# dac.net
KiCad netlist of a schematic drawn in EAGLE
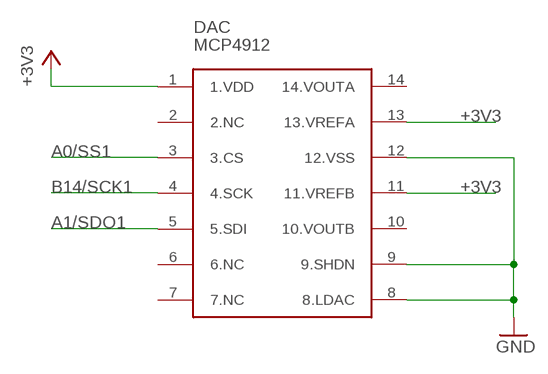
[diagram p0: schematic, sheet 1]
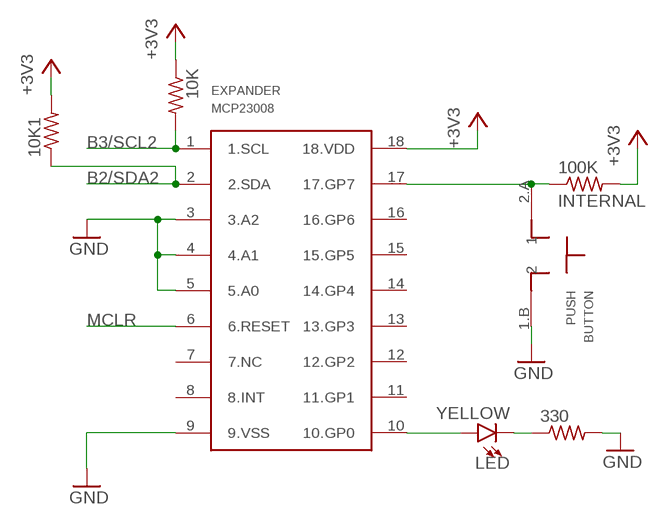
[diagram p1: schematic, sheet 2]

(export (version "E")
  (design (tool "Eeschema 10.0.6"))
  (components
    (comp (ref "DAC")
      (value "MCP4912")
      (footprint "eagle-import:MCP4912")
      (libsource (lib "eagle-import") (part "MCP4912"))
    )
    (comp (ref "10K")
      (value "R-US_R0603")
      (footprint "eagle-import:R0603")
      (libsource (lib "eagle-import") (part "R-US_R0603"))
    )
    (comp (ref "10K1")
      (value "R-US_R0603")
      (footprint "eagle-import:R0603")
      (libsource (lib "eagle-import") (part "R-US_R0603"))
    )
    (comp (ref "100K")
      (value "INTERNAL")
      (footprint "eagle-import:R0603")
      (libsource (lib "eagle-import") (part "R-US_R0603"))
    )
    (comp (ref "330")
      (value "R-US_R0603")
      (footprint "eagle-import:R0603")
      (libsource (lib "eagle-import") (part "R-US_R0603"))
    )
    (comp (ref "BUTTON")
      (value "PUSH")
      (footprint "eagle-import:NU32V7_MOM_SW")
      (libsource (lib "eagle-import") (part "PUSH"))
    )
    (comp (ref "EXPANDER")
      (value "MCP23008")
      (footprint "eagle-import:MCP23008")
      (libsource (lib "eagle-import") (part "MCP23008"))
    )
    (comp (ref "LED")
      (value "YELLOW")
      (footprint "eagle-import:LED-0603")
      (libsource (lib "eagle-import") (part "LED-RED0603"))
    )
  )
  (nets
    (net (code "1") (name "+3V3") (class "Default")
      (node (ref "100K") (pin "2") (pinfunction "2_2") (pintype "passive"))
      (node (ref "10K") (pin "1") (pinfunction "1_1") (pintype "passive"))
      (node (ref "10K1") (pin "2") (pinfunction "2_2") (pintype "passive"))
      (node (ref "DAC") (pin "1") (pinfunction "1.VDD_1") (pintype "bidirectional"))
      (node (ref "DAC") (pin "11") (pinfunction "11.VREFB_11") (pintype "bidirectional"))
      (node (ref "DAC") (pin "13") (pinfunction "13.VREFA_13") (pintype "bidirectional"))
      (node (ref "EXPANDER") (pin "18") (pinfunction "18.VDD_18") (pintype "bidirectional"))
    )
    (net (code "2") (name "A0{slash}SS1") (class "Default")
      (node (ref "DAC") (pin "3") (pinfunction "3.CS_3") (pintype "bidirectional"))
    )
    (net (code "3") (name "A1{slash}SDO1") (class "Default")
      (node (ref "DAC") (pin "5") (pinfunction "5.SDI_5") (pintype "bidirectional"))
    )
    (net (code "4") (name "B2{slash}SDA2") (class "Default")
      (node (ref "10K1") (pin "1") (pinfunction "1_1") (pintype "passive"))
      (node (ref "EXPANDER") (pin "2") (pinfunction "2.SDA_2") (pintype "bidirectional"))
    )
    (net (code "5") (name "B3{slash}SCL2") (class "Default")
      (node (ref "10K") (pin "2") (pinfunction "2_2") (pintype "passive"))
      (node (ref "EXPANDER") (pin "1") (pinfunction "1.SCL_1") (pintype "bidirectional"))
    )
    (net (code "6") (name "B14{slash}SCK1") (class "Default")
      (node (ref "DAC") (pin "4") (pinfunction "4.SCK_4") (pintype "bidirectional"))
    )
    (net (code "7") (name "GND") (class "Default")
      (node (ref "330") (pin "2") (pinfunction "2_2") (pintype "passive"))
      (node (ref "BUTTON") (pin "1.B") (pinfunction "2_1.B") (pintype "bidirectional"))
      (node (ref "DAC") (pin "12") (pinfunction "12.VSS_12") (pintype "bidirectional"))
      (node (ref "DAC") (pin "8") (pinfunction "8.LDAC_8") (pintype "bidirectional"))
      (node (ref "DAC") (pin "9") (pinfunction "9.SHDN_9") (pintype "bidirectional"))
      (node (ref "EXPANDER") (pin "3") (pinfunction "3.A2_3") (pintype "bidirectional"))
      (node (ref "EXPANDER") (pin "4") (pinfunction "4.A1_4") (pintype "bidirectional"))
      (node (ref "EXPANDER") (pin "5") (pinfunction "5.A0_5") (pintype "bidirectional"))
      (node (ref "EXPANDER") (pin "9") (pinfunction "9.VSS_9") (pintype "bidirectional"))
    )
    (net (code "8") (name "MCLR") (class "Default")
      (node (ref "EXPANDER") (pin "6") (pinfunction "6.RESET_6") (pintype "bidirectional"))
    )
    (net (code "9") (name "Net-(330-Pad1)") (class "Default")
      (node (ref "330") (pin "1") (pinfunction "1_1") (pintype "passive"))
      (node (ref "LED") (pin "C") (pinfunction "C_C") (pintype "passive"))
    )
    (net (code "10") (name "Net-(BUTTON-1)") (class "Default")
      (node (ref "100K") (pin "1") (pinfunction "1_1") (pintype "passive"))
      (node (ref "BUTTON") (pin "2.A") (pinfunction "1_2.A") (pintype "bidirectional"))
      (node (ref "EXPANDER") (pin "17") (pinfunction "17.GP7_17") (pintype "bidirectional"))
    )
    (net (code "11") (name "Net-(EXPANDER-10.GP0)") (class "Default")
      (node (ref "EXPANDER") (pin "10") (pinfunction "10.GP0_10") (pintype "bidirectional"))
      (node (ref "LED") (pin "A") (pinfunction "A_A") (pintype "passive"))
    )
    (net (code "12") (name "unconnected-(DAC-2.NC-Pad2)") (class "Default")
      (node (ref "DAC") (pin "2") (pinfunction "2.NC_2") (pintype "bidirectional"))
    )
    (net (code "13") (name "unconnected-(DAC-6.NC-Pad6)") (class "Default")
      (node (ref "DAC") (pin "6") (pinfunction "6.NC_6") (pintype "bidirectional"))
    )
    (net (code "14") (name "unconnected-(DAC-7.NC-Pad7)") (class "Default")
      (node (ref "DAC") (pin "7") (pinfunction "7.NC_7") (pintype "bidirectional"))
    )
    (net (code "15") (name "unconnected-(DAC-10.VOUTB-Pad10)") (class "Default")
      (node (ref "DAC") (pin "10") (pinfunction "10.VOUTB_10") (pintype "bidirectional"))
    )
    (net (code "16") (name "unconnected-(DAC-14.VOUTA-Pad14)") (class "Default")
      (node (ref "DAC") (pin "14") (pinfunction "14.VOUTA_14") (pintype "bidirectional"))
    )
    (net (code "17") (name "unconnected-(EXPANDER-7.NC-Pad7)") (class "Default")
      (node (ref "EXPANDER") (pin "7") (pinfunction "7.NC_7") (pintype "bidirectional"))
    )
    (net (code "18") (name "unconnected-(EXPANDER-8.INT-Pad8)") (class "Default")
      (node (ref "EXPANDER") (pin "8") (pinfunction "8.INT_8") (pintype "bidirectional"))
    )
    (net (code "19") (name "unconnected-(EXPANDER-11.GP1-Pad11)") (class "Default")
      (node (ref "EXPANDER") (pin "11") (pinfunction "11.GP1_11") (pintype "bidirectional"))
    )
    (net (code "20") (name "unconnected-(EXPANDER-12.GP2-Pad12)") (class "Default")
      (node (ref "EXPANDER") (pin "12") (pinfunction "12.GP2_12") (pintype "bidirectional"))
    )
    (net (code "21") (name "unconnected-(EXPANDER-13.GP3-Pad13)") (class "Default")
      (node (ref "EXPANDER") (pin "13") (pinfunction "13.GP3_13") (pintype "bidirectional"))
    )
    (net (code "22") (name "unconnected-(EXPANDER-14.GP4-Pad14)") (class "Default")
      (node (ref "EXPANDER") (pin "14") (pinfunction "14.GP4_14") (pintype "bidirectional"))
    )
    (net (code "23") (name "unconnected-(EXPANDER-15.GP5-Pad15)") (class "Default")
      (node (ref "EXPANDER") (pin "15") (pinfunction "15.GP5_15") (pintype "bidirectional"))
    )
    (net (code "24") (name "unconnected-(EXPANDER-16.GP6-Pad16)") (class "Default")
      (node (ref "EXPANDER") (pin "16") (pinfunction "16.GP6_16") (pintype "bidirectional"))
    )
  )
)
